# PCB_Eagle.net
KiCad netlist of a schematic drawn in EAGLE
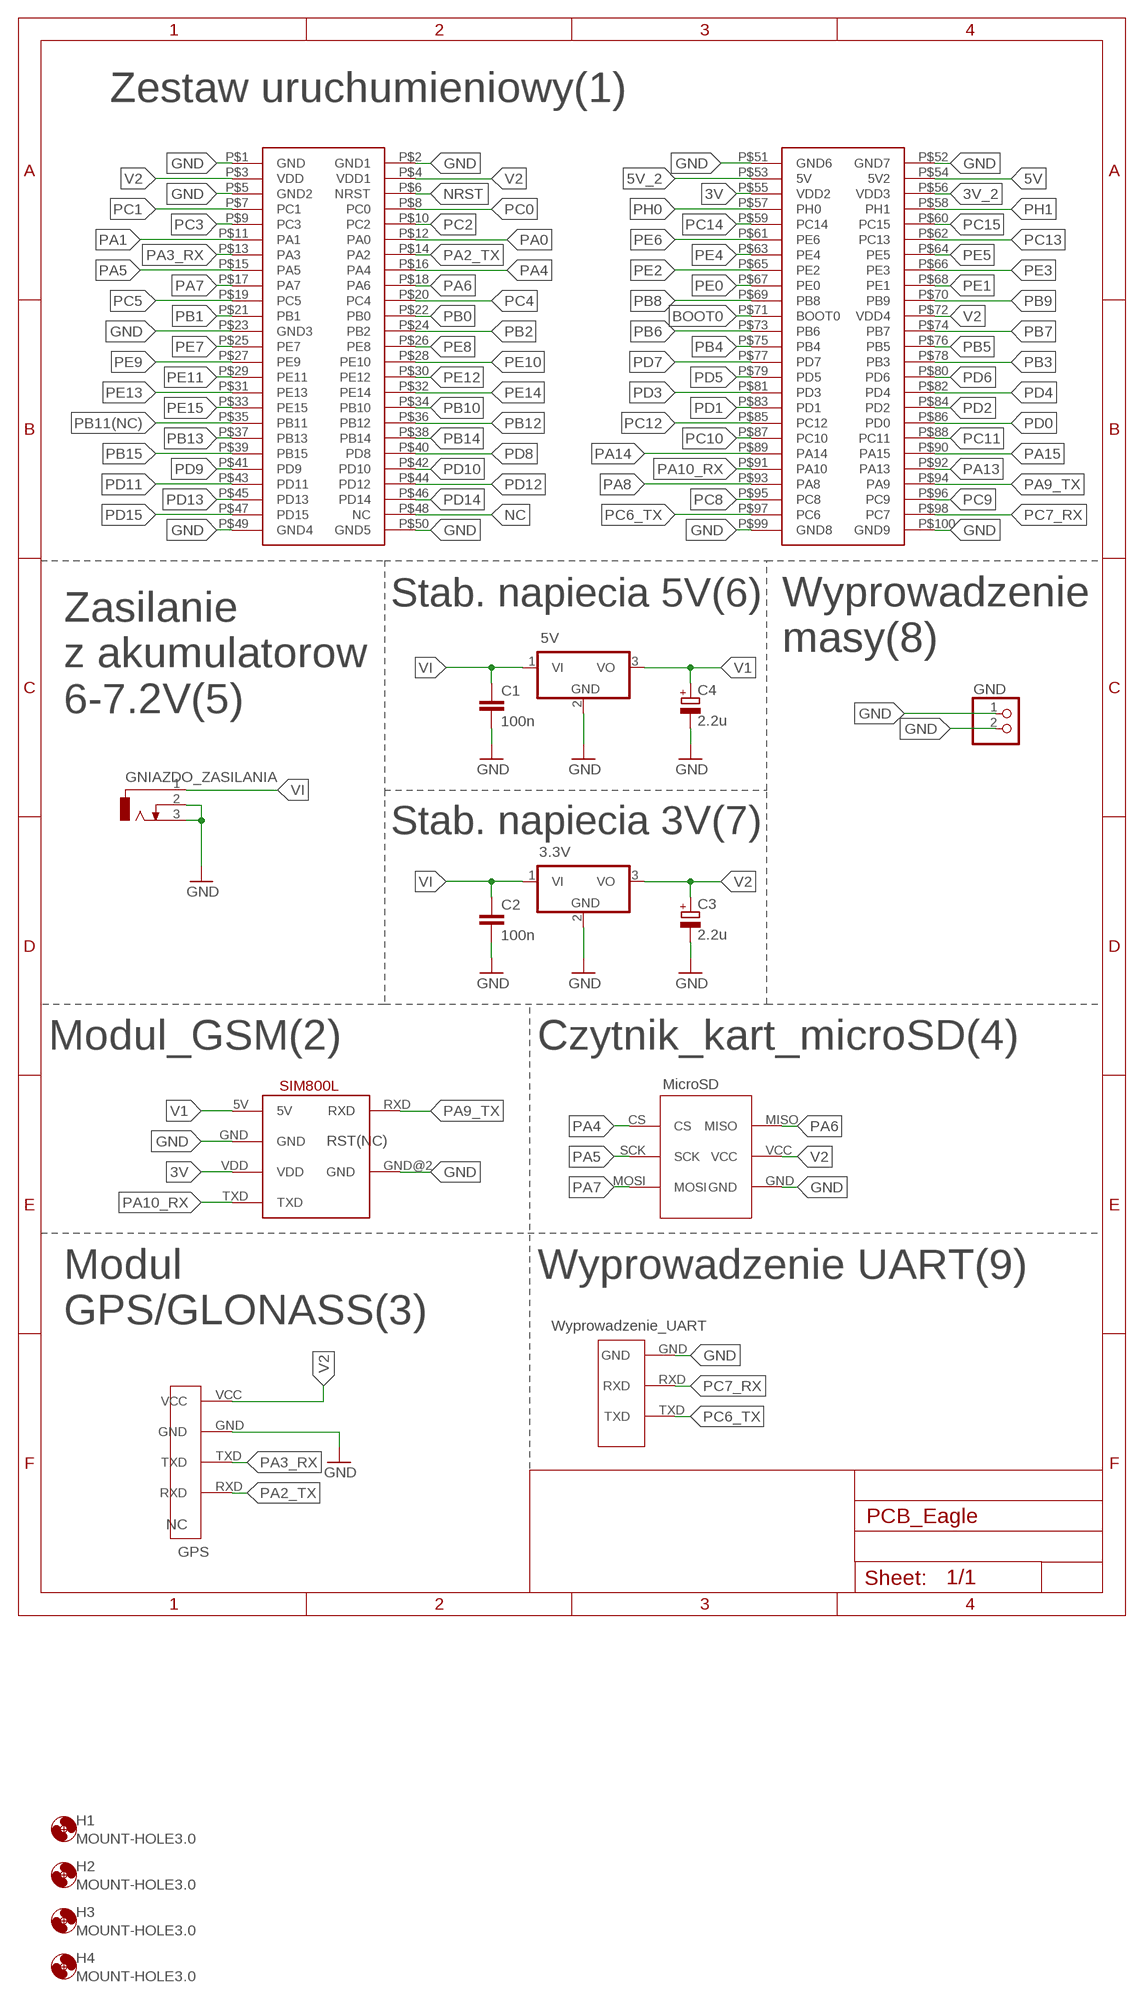
[diagram p0: schematic, sheet 1]

(export (version "E")
  (design (tool "Eeschema 10.0.6"))
  (components
    (comp (ref "3.3V")
      (value "7805TV")
      (footprint "eagle-import:TO220V")
      (libsource (lib "eagle-import") (part "78TV05"))
    )
    (comp (ref "5V")
      (value "7805TV")
      (footprint "eagle-import:TO220V")
      (libsource (lib "eagle-import") (part "78TV05"))
    )
    (comp (ref "C1")
      (value "100n")
      (footprint "eagle-import:C1206K")
      (libsource (lib "eagle-import") (part "C-EUC1206K"))
    )
    (comp (ref "C2")
      (value "100n")
      (footprint "eagle-import:C1206K")
      (libsource (lib "eagle-import") (part "C-EUC1206K"))
    )
    (comp (ref "C3")
      (value "2.2u")
      (footprint "eagle-import:A_3216-18W")
      (libsource (lib "eagle-import") (part "CPOL-EUA/3216-18W"))
    )
    (comp (ref "C4")
      (value "2.2u")
      (footprint "eagle-import:A_3216-18W")
      (libsource (lib "eagle-import") (part "CPOL-EUA/3216-18W"))
    )
    (comp (ref "GND")
      (value "PINHD-1X2")
      (footprint "eagle-import:1X02")
      (libsource (lib "eagle-import") (part "PINHD-1X2"))
    )
    (comp (ref "GNIAZDO_ZASILANIA")
      (value "WEJSCIE_VCC")
      (footprint "eagle-import:DCJ0202")
      (libsource (lib "eagle-import") (part "WEJSCIE_VCC"))
    )
    (comp (ref "H1")
      (value "MOUNT-HOLE3.0")
      (footprint "eagle-import:3,0")
      (libsource (lib "eagle-import") (part "MOUNT-HOLE3.0"))
    )
    (comp (ref "H2")
      (value "MOUNT-HOLE3.0")
      (footprint "eagle-import:3,0")
      (libsource (lib "eagle-import") (part "MOUNT-HOLE3.0"))
    )
    (comp (ref "H3")
      (value "MOUNT-HOLE3.0")
      (footprint "eagle-import:3,0")
      (libsource (lib "eagle-import") (part "MOUNT-HOLE3.0"))
    )
    (comp (ref "H4")
      (value "MOUNT-HOLE3.0")
      (footprint "eagle-import:3,0")
      (libsource (lib "eagle-import") (part "MOUNT-HOLE3.0"))
    )
    (comp (ref "U$1")
      (value "MODUL_GPS")
      (footprint "eagle-import:MODUL_GPS")
      (libsource (lib "eagle-import") (part "MODUL_GPS"))
    )
    (comp (ref "U$3")
      (value "MODUL_GSM")
      (footprint "eagle-import:MODUL_GSM")
      (libsource (lib "eagle-import") (part "MODUL_GSM"))
    )
    (comp (ref "U$4")
      (value "STM32F4-DISCOVERY")
      (footprint "eagle-import:STM32F4-DISCOVERY")
      (libsource (lib "eagle-import") (part "STM32F4-DISCOVERY"))
    )
    (comp (ref "U$5")
      (value "WYPROWADZENIE_UART")
      (footprint "eagle-import:WYPROWADZENIE_UART")
      (libsource (lib "eagle-import") (part "WYPROWADZENIE_UART"))
    )
    (comp (ref "U$6")
      (value "MICROSD")
      (footprint "eagle-import:MICROSD")
      (libsource (lib "eagle-import") (part "MICROSD"))
    )
  )
  (nets
    (net (code "1") (name "3V") (class "Default")
      (node (ref "U$3") (pin "VDD") (pinfunction "VDD_VDD") (pintype "bidirectional"))
      (node (ref "U$4") (pin "P$55") (pinfunction "VDD2_P$55") (pintype "bidirectional"))
    )
    (net (code "2") (name "3V_2") (class "Default")
      (node (ref "U$4") (pin "P$56") (pinfunction "VDD3_P$56") (pintype "bidirectional"))
    )
    (net (code "3") (name "5V") (class "Default")
      (node (ref "U$4") (pin "P$54") (pinfunction "5V2_P$54") (pintype "bidirectional"))
    )
    (net (code "4") (name "5V_2") (class "Default")
      (node (ref "U$4") (pin "P$53") (pinfunction "5V_P$53") (pintype "bidirectional"))
    )
    (net (code "5") (name "BOOT0") (class "Default")
      (node (ref "U$4") (pin "P$71") (pinfunction "BOOT0_P$71") (pintype "bidirectional"))
    )
    (net (code "6") (name "GND") (class "Default")
      (node (ref "3.3V") (pin "2") (pinfunction "GND_2") (pintype "passive"))
      (node (ref "5V") (pin "2") (pinfunction "GND_2") (pintype "passive"))
      (node (ref "C1") (pin "2") (pinfunction "2_2") (pintype "passive"))
      (node (ref "C2") (pin "2") (pinfunction "2_2") (pintype "passive"))
      (node (ref "C3") (pin "-") (pinfunction "-_-") (pintype "passive"))
      (node (ref "C4") (pin "-") (pinfunction "-_-") (pintype "passive"))
      (node (ref "GND") (pin "1") (pinfunction "1_1") (pintype "passive"))
      (node (ref "GND") (pin "2") (pinfunction "2_2") (pintype "passive"))
      (node (ref "GNIAZDO_ZASILANIA") (pin "2") (pinfunction "2_2") (pintype "passive"))
      (node (ref "GNIAZDO_ZASILANIA") (pin "3") (pinfunction "3_3") (pintype "passive"))
      (node (ref "U$1") (pin "GND") (pinfunction "GND_GND") (pintype "bidirectional"))
      (node (ref "U$3") (pin "GND") (pinfunction "GND_GND") (pintype "bidirectional"))
      (node (ref "U$3") (pin "GND@2") (pinfunction "GND_GND@2") (pintype "bidirectional"))
      (node (ref "U$4") (pin "P$1") (pinfunction "GND_P$1") (pintype "bidirectional"))
      (node (ref "U$4") (pin "P$100") (pinfunction "GND9_P$100") (pintype "bidirectional"))
      (node (ref "U$4") (pin "P$2") (pinfunction "GND1_P$2") (pintype "bidirectional"))
      (node (ref "U$4") (pin "P$23") (pinfunction "GND3_P$23") (pintype "bidirectional"))
      (node (ref "U$4") (pin "P$49") (pinfunction "GND4_P$49") (pintype "bidirectional"))
      (node (ref "U$4") (pin "P$5") (pinfunction "GND2_P$5") (pintype "bidirectional"))
      (node (ref "U$4") (pin "P$50") (pinfunction "GND5_P$50") (pintype "bidirectional"))
      (node (ref "U$4") (pin "P$51") (pinfunction "GND6_P$51") (pintype "bidirectional"))
      (node (ref "U$4") (pin "P$52") (pinfunction "GND7_P$52") (pintype "bidirectional"))
      (node (ref "U$4") (pin "P$99") (pinfunction "GND8_P$99") (pintype "bidirectional"))
      (node (ref "U$5") (pin "GND") (pinfunction "GND_GND") (pintype "bidirectional"))
      (node (ref "U$6") (pin "GND") (pinfunction "GND_GND") (pintype "bidirectional"))
    )
    (net (code "7") (name "NC") (class "Default")
      (node (ref "U$4") (pin "P$48") (pinfunction "NC_P$48") (pintype "bidirectional"))
    )
    (net (code "8") (name "NRST") (class "Default")
      (node (ref "U$4") (pin "P$6") (pinfunction "NRST_P$6") (pintype "bidirectional"))
    )
    (net (code "9") (name "PA0") (class "Default")
      (node (ref "U$4") (pin "P$12") (pinfunction "PA0_P$12") (pintype "bidirectional"))
    )
    (net (code "10") (name "PA1") (class "Default")
      (node (ref "U$4") (pin "P$11") (pinfunction "PA1_P$11") (pintype "bidirectional"))
    )
    (net (code "11") (name "PA2_TX") (class "Default")
      (node (ref "U$1") (pin "RXD") (pinfunction "RXD_RXD") (pintype "bidirectional"))
      (node (ref "U$4") (pin "P$14") (pinfunction "PA2_P$14") (pintype "bidirectional"))
    )
    (net (code "12") (name "PA3_RX") (class "Default")
      (node (ref "U$1") (pin "TXD") (pinfunction "TXD_TXD") (pintype "bidirectional"))
      (node (ref "U$4") (pin "P$13") (pinfunction "PA3_P$13") (pintype "bidirectional"))
    )
    (net (code "13") (name "PA4") (class "Default")
      (node (ref "U$4") (pin "P$16") (pinfunction "PA4_P$16") (pintype "bidirectional"))
      (node (ref "U$6") (pin "CS") (pinfunction "CS_CS") (pintype "bidirectional"))
    )
    (net (code "14") (name "PA5") (class "Default")
      (node (ref "U$4") (pin "P$15") (pinfunction "PA5_P$15") (pintype "bidirectional"))
      (node (ref "U$6") (pin "SCK") (pinfunction "SCK_SCK") (pintype "bidirectional"))
    )
    (net (code "15") (name "PA6") (class "Default")
      (node (ref "U$4") (pin "P$18") (pinfunction "PA6_P$18") (pintype "bidirectional"))
      (node (ref "U$6") (pin "MISO") (pinfunction "MISO_MISO") (pintype "bidirectional"))
    )
    (net (code "16") (name "PA7") (class "Default")
      (node (ref "U$4") (pin "P$17") (pinfunction "PA7_P$17") (pintype "bidirectional"))
      (node (ref "U$6") (pin "MOSI") (pinfunction "MOSI_MOSI") (pintype "bidirectional"))
    )
    (net (code "17") (name "PA8") (class "Default")
      (node (ref "U$4") (pin "P$93") (pinfunction "PA8_P$93") (pintype "bidirectional"))
    )
    (net (code "18") (name "PA9_TX") (class "Default")
      (node (ref "U$3") (pin "RXD") (pinfunction "RXD_RXD") (pintype "bidirectional"))
      (node (ref "U$4") (pin "P$94") (pinfunction "PA9_P$94") (pintype "bidirectional"))
    )
    (net (code "19") (name "PA10_RX") (class "Default")
      (node (ref "U$3") (pin "TXD") (pinfunction "TXD_TXD") (pintype "bidirectional"))
      (node (ref "U$4") (pin "P$91") (pinfunction "PA10_P$91") (pintype "bidirectional"))
    )
    (net (code "20") (name "PA13") (class "Default")
      (node (ref "U$4") (pin "P$92") (pinfunction "PA13_P$92") (pintype "bidirectional"))
    )
    (net (code "21") (name "PA14") (class "Default")
      (node (ref "U$4") (pin "P$89") (pinfunction "PA14_P$89") (pintype "bidirectional"))
    )
    (net (code "22") (name "PA15") (class "Default")
      (node (ref "U$4") (pin "P$90") (pinfunction "PA15_P$90") (pintype "bidirectional"))
    )
    (net (code "23") (name "PB0") (class "Default")
      (node (ref "U$4") (pin "P$22") (pinfunction "PB0_P$22") (pintype "bidirectional"))
    )
    (net (code "24") (name "PB1") (class "Default")
      (node (ref "U$4") (pin "P$21") (pinfunction "PB1_P$21") (pintype "bidirectional"))
    )
    (net (code "25") (name "PB2") (class "Default")
      (node (ref "U$4") (pin "P$24") (pinfunction "PB2_P$24") (pintype "bidirectional"))
    )
    (net (code "26") (name "PB3") (class "Default")
      (node (ref "U$4") (pin "P$78") (pinfunction "PB3_P$78") (pintype "bidirectional"))
    )
    (net (code "27") (name "PB4") (class "Default")
      (node (ref "U$4") (pin "P$75") (pinfunction "PB4_P$75") (pintype "bidirectional"))
    )
    (net (code "28") (name "PB5") (class "Default")
      (node (ref "U$4") (pin "P$76") (pinfunction "PB5_P$76") (pintype "bidirectional"))
    )
    (net (code "29") (name "PB6") (class "Default")
      (node (ref "U$4") (pin "P$73") (pinfunction "PB6_P$73") (pintype "bidirectional"))
    )
    (net (code "30") (name "PB7") (class "Default")
      (node (ref "U$4") (pin "P$74") (pinfunction "PB7_P$74") (pintype "bidirectional"))
    )
    (net (code "31") (name "PB8") (class "Default")
      (node (ref "U$4") (pin "P$69") (pinfunction "PB8_P$69") (pintype "bidirectional"))
    )
    (net (code "32") (name "PB9") (class "Default")
      (node (ref "U$4") (pin "P$70") (pinfunction "PB9_P$70") (pintype "bidirectional"))
    )
    (net (code "33") (name "PB10") (class "Default")
      (node (ref "U$4") (pin "P$34") (pinfunction "PB10_P$34") (pintype "bidirectional"))
    )
    (net (code "34") (name "PB11(NC)") (class "Default")
      (node (ref "U$4") (pin "P$35") (pinfunction "PB11_P$35") (pintype "bidirectional"))
    )
    (net (code "35") (name "PB12") (class "Default")
      (node (ref "U$4") (pin "P$36") (pinfunction "PB12_P$36") (pintype "bidirectional"))
    )
    (net (code "36") (name "PB13") (class "Default")
      (node (ref "U$4") (pin "P$37") (pinfunction "PB13_P$37") (pintype "bidirectional"))
    )
    (net (code "37") (name "PB14") (class "Default")
      (node (ref "U$4") (pin "P$38") (pinfunction "PB14_P$38") (pintype "bidirectional"))
    )
    (net (code "38") (name "PB15") (class "Default")
      (node (ref "U$4") (pin "P$39") (pinfunction "PB15_P$39") (pintype "bidirectional"))
    )
    (net (code "39") (name "PC0") (class "Default")
      (node (ref "U$4") (pin "P$8") (pinfunction "PC0_P$8") (pintype "bidirectional"))
    )
    (net (code "40") (name "PC1") (class "Default")
      (node (ref "U$4") (pin "P$7") (pinfunction "PC1_P$7") (pintype "bidirectional"))
    )
    (net (code "41") (name "PC2") (class "Default")
      (node (ref "U$4") (pin "P$10") (pinfunction "PC2_P$10") (pintype "bidirectional"))
    )
    (net (code "42") (name "PC3") (class "Default")
      (node (ref "U$4") (pin "P$9") (pinfunction "PC3_P$9") (pintype "bidirectional"))
    )
    (net (code "43") (name "PC4") (class "Default")
      (node (ref "U$4") (pin "P$20") (pinfunction "PC4_P$20") (pintype "bidirectional"))
    )
    (net (code "44") (name "PC5") (class "Default")
      (node (ref "U$4") (pin "P$19") (pinfunction "PC5_P$19") (pintype "bidirectional"))
    )
    (net (code "45") (name "PC6_TX") (class "Default")
      (node (ref "U$4") (pin "P$97") (pinfunction "PC6_P$97") (pintype "bidirectional"))
      (node (ref "U$5") (pin "TXD") (pinfunction "TXD_TXD") (pintype "bidirectional"))
    )
    (net (code "46") (name "PC7_RX") (class "Default")
      (node (ref "U$4") (pin "P$98") (pinfunction "PC7_P$98") (pintype "bidirectional"))
      (node (ref "U$5") (pin "RXD") (pinfunction "RXD_RXD") (pintype "bidirectional"))
    )
    (net (code "47") (name "PC8") (class "Default")
      (node (ref "U$4") (pin "P$95") (pinfunction "PC8_P$95") (pintype "bidirectional"))
    )
    (net (code "48") (name "PC9") (class "Default")
      (node (ref "U$4") (pin "P$96") (pinfunction "PC9_P$96") (pintype "bidirectional"))
    )
    (net (code "49") (name "PC10") (class "Default")
      (node (ref "U$4") (pin "P$87") (pinfunction "PC10_P$87") (pintype "bidirectional"))
    )
    (net (code "50") (name "PC11") (class "Default")
      (node (ref "U$4") (pin "P$88") (pinfunction "PC11_P$88") (pintype "bidirectional"))
    )
    (net (code "51") (name "PC12") (class "Default")
      (node (ref "U$4") (pin "P$85") (pinfunction "PC12_P$85") (pintype "bidirectional"))
    )
    (net (code "52") (name "PC13") (class "Default")
      (node (ref "U$4") (pin "P$62") (pinfunction "PC13_P$62") (pintype "bidirectional"))
    )
    (net (code "53") (name "PC14") (class "Default")
      (node (ref "U$4") (pin "P$59") (pinfunction "PC14_P$59") (pintype "bidirectional"))
    )
    (net (code "54") (name "PC15") (class "Default")
      (node (ref "U$4") (pin "P$60") (pinfunction "PC15_P$60") (pintype "bidirectional"))
    )
    (net (code "55") (name "PD0") (class "Default")
      (node (ref "U$4") (pin "P$86") (pinfunction "PD0_P$86") (pintype "bidirectional"))
    )
    (net (code "56") (name "PD1") (class "Default")
      (node (ref "U$4") (pin "P$83") (pinfunction "PD1_P$83") (pintype "bidirectional"))
    )
    (net (code "57") (name "PD2") (class "Default")
      (node (ref "U$4") (pin "P$84") (pinfunction "PD2_P$84") (pintype "bidirectional"))
    )
    (net (code "58") (name "PD3") (class "Default")
      (node (ref "U$4") (pin "P$81") (pinfunction "PD3_P$81") (pintype "bidirectional"))
    )
    (net (code "59") (name "PD4") (class "Default")
      (node (ref "U$4") (pin "P$82") (pinfunction "PD4_P$82") (pintype "bidirectional"))
    )
    (net (code "60") (name "PD5") (class "Default")
      (node (ref "U$4") (pin "P$79") (pinfunction "PD5_P$79") (pintype "bidirectional"))
    )
    (net (code "61") (name "PD6") (class "Default")
      (node (ref "U$4") (pin "P$80") (pinfunction "PD6_P$80") (pintype "bidirectional"))
    )
    (net (code "62") (name "PD7") (class "Default")
      (node (ref "U$4") (pin "P$77") (pinfunction "PD7_P$77") (pintype "bidirectional"))
    )
    (net (code "63") (name "PD8") (class "Default")
      (node (ref "U$4") (pin "P$40") (pinfunction "PD8_P$40") (pintype "bidirectional"))
    )
    (net (code "64") (name "PD9") (class "Default")
      (node (ref "U$4") (pin "P$41") (pinfunction "PD9_P$41") (pintype "bidirectional"))
    )
    (net (code "65") (name "PD10") (class "Default")
      (node (ref "U$4") (pin "P$42") (pinfunction "PD10_P$42") (pintype "bidirectional"))
    )
    (net (code "66") (name "PD11") (class "Default")
      (node (ref "U$4") (pin "P$43") (pinfunction "PD11_P$43") (pintype "bidirectional"))
    )
    (net (code "67") (name "PD12") (class "Default")
      (node (ref "U$4") (pin "P$44") (pinfunction "PD12_P$44") (pintype "bidirectional"))
    )
    (net (code "68") (name "PD13") (class "Default")
      (node (ref "U$4") (pin "P$45") (pinfunction "PD13_P$45") (pintype "bidirectional"))
    )
    (net (code "69") (name "PD14") (class "Default")
      (node (ref "U$4") (pin "P$46") (pinfunction "PD14_P$46") (pintype "bidirectional"))
    )
    (net (code "70") (name "PD15") (class "Default")
      (node (ref "U$4") (pin "P$47") (pinfunction "PD15_P$47") (pintype "bidirectional"))
    )
    (net (code "71") (name "PE0") (class "Default")
      (node (ref "U$4") (pin "P$67") (pinfunction "PE0_P$67") (pintype "bidirectional"))
    )
    (net (code "72") (name "PE1") (class "Default")
      (node (ref "U$4") (pin "P$68") (pinfunction "PE1_P$68") (pintype "bidirectional"))
    )
    (net (code "73") (name "PE2") (class "Default")
      (node (ref "U$4") (pin "P$65") (pinfunction "PE2_P$65") (pintype "bidirectional"))
    )
    (net (code "74") (name "PE3") (class "Default")
      (node (ref "U$4") (pin "P$66") (pinfunction "PE3_P$66") (pintype "bidirectional"))
    )
    (net (code "75") (name "PE4") (class "Default")
      (node (ref "U$4") (pin "P$63") (pinfunction "PE4_P$63") (pintype "bidirectional"))
    )
    (net (code "76") (name "PE5") (class "Default")
      (node (ref "U$4") (pin "P$64") (pinfunction "PE5_P$64") (pintype "bidirectional"))
    )
    (net (code "77") (name "PE6") (class "Default")
      (node (ref "U$4") (pin "P$61") (pinfunction "PE6_P$61") (pintype "bidirectional"))
    )
    (net (code "78") (name "PE7") (class "Default")
      (node (ref "U$4") (pin "P$25") (pinfunction "PE7_P$25") (pintype "bidirectional"))
    )
    (net (code "79") (name "PE8") (class "Default")
      (node (ref "U$4") (pin "P$26") (pinfunction "PE8_P$26") (pintype "bidirectional"))
    )
    (net (code "80") (name "PE9") (class "Default")
      (node (ref "U$4") (pin "P$27") (pinfunction "PE9_P$27") (pintype "bidirectional"))
    )
    (net (code "81") (name "PE10") (class "Default")
      (node (ref "U$4") (pin "P$28") (pinfunction "PE10_P$28") (pintype "bidirectional"))
    )
    (net (code "82") (name "PE11") (class "Default")
      (node (ref "U$4") (pin "P$29") (pinfunction "PE11_P$29") (pintype "bidirectional"))
    )
    (net (code "83") (name "PE12") (class "Default")
      (node (ref "U$4") (pin "P$30") (pinfunction "PE12_P$30") (pintype "bidirectional"))
    )
    (net (code "84") (name "PE13") (class "Default")
      (node (ref "U$4") (pin "P$31") (pinfunction "PE13_P$31") (pintype "bidirectional"))
    )
    (net (code "85") (name "PE14") (class "Default")
      (node (ref "U$4") (pin "P$32") (pinfunction "PE14_P$32") (pintype "bidirectional"))
    )
    (net (code "86") (name "PE15") (class "Default")
      (node (ref "U$4") (pin "P$33") (pinfunction "PE15_P$33") (pintype "bidirectional"))
    )
    (net (code "87") (name "PH0") (class "Default")
      (node (ref "U$4") (pin "P$57") (pinfunction "PH0_P$57") (pintype "bidirectional"))
    )
    (net (code "88") (name "PH1") (class "Default")
      (node (ref "U$4") (pin "P$58") (pinfunction "PH1_P$58") (pintype "bidirectional"))
    )
    (net (code "89") (name "V1") (class "Default")
      (node (ref "5V") (pin "3") (pinfunction "VO_3") (pintype "passive"))
      (node (ref "C4") (pin "+") (pinfunction "+_+") (pintype "passive"))
      (node (ref "U$3") (pin "5V") (pinfunction "5V_5V") (pintype "bidirectional"))
    )
    (net (code "90") (name "V2") (class "Default")
      (node (ref "3.3V") (pin "3") (pinfunction "VO_3") (pintype "passive"))
      (node (ref "C3") (pin "+") (pinfunction "+_+") (pintype "passive"))
      (node (ref "U$1") (pin "VCC") (pinfunction "VCC_VCC") (pintype "bidirectional"))
      (node (ref "U$4") (pin "P$3") (pinfunction "VDD_P$3") (pintype "bidirectional"))
      (node (ref "U$4") (pin "P$4") (pinfunction "VDD1_P$4") (pintype "bidirectional"))
      (node (ref "U$4") (pin "P$72") (pinfunction "VDD4_P$72") (pintype "bidirectional"))
      (node (ref "U$6") (pin "VCC") (pinfunction "VCC_VCC") (pintype "bidirectional"))
    )
    (net (code "91") (name "VI") (class "Default")
      (node (ref "3.3V") (pin "1") (pinfunction "VI_1") (pintype "input"))
      (node (ref "5V") (pin "1") (pinfunction "VI_1") (pintype "input"))
      (node (ref "C1") (pin "1") (pinfunction "1_1") (pintype "passive"))
      (node (ref "C2") (pin "1") (pinfunction "1_1") (pintype "passive"))
      (node (ref "GNIAZDO_ZASILANIA") (pin "1") (pinfunction "1_1") (pintype "passive"))
    )
  )
)
